# Slave1_flying_pcb_v1.net
KiCad netlist of a schematic drawn in Altium Designer
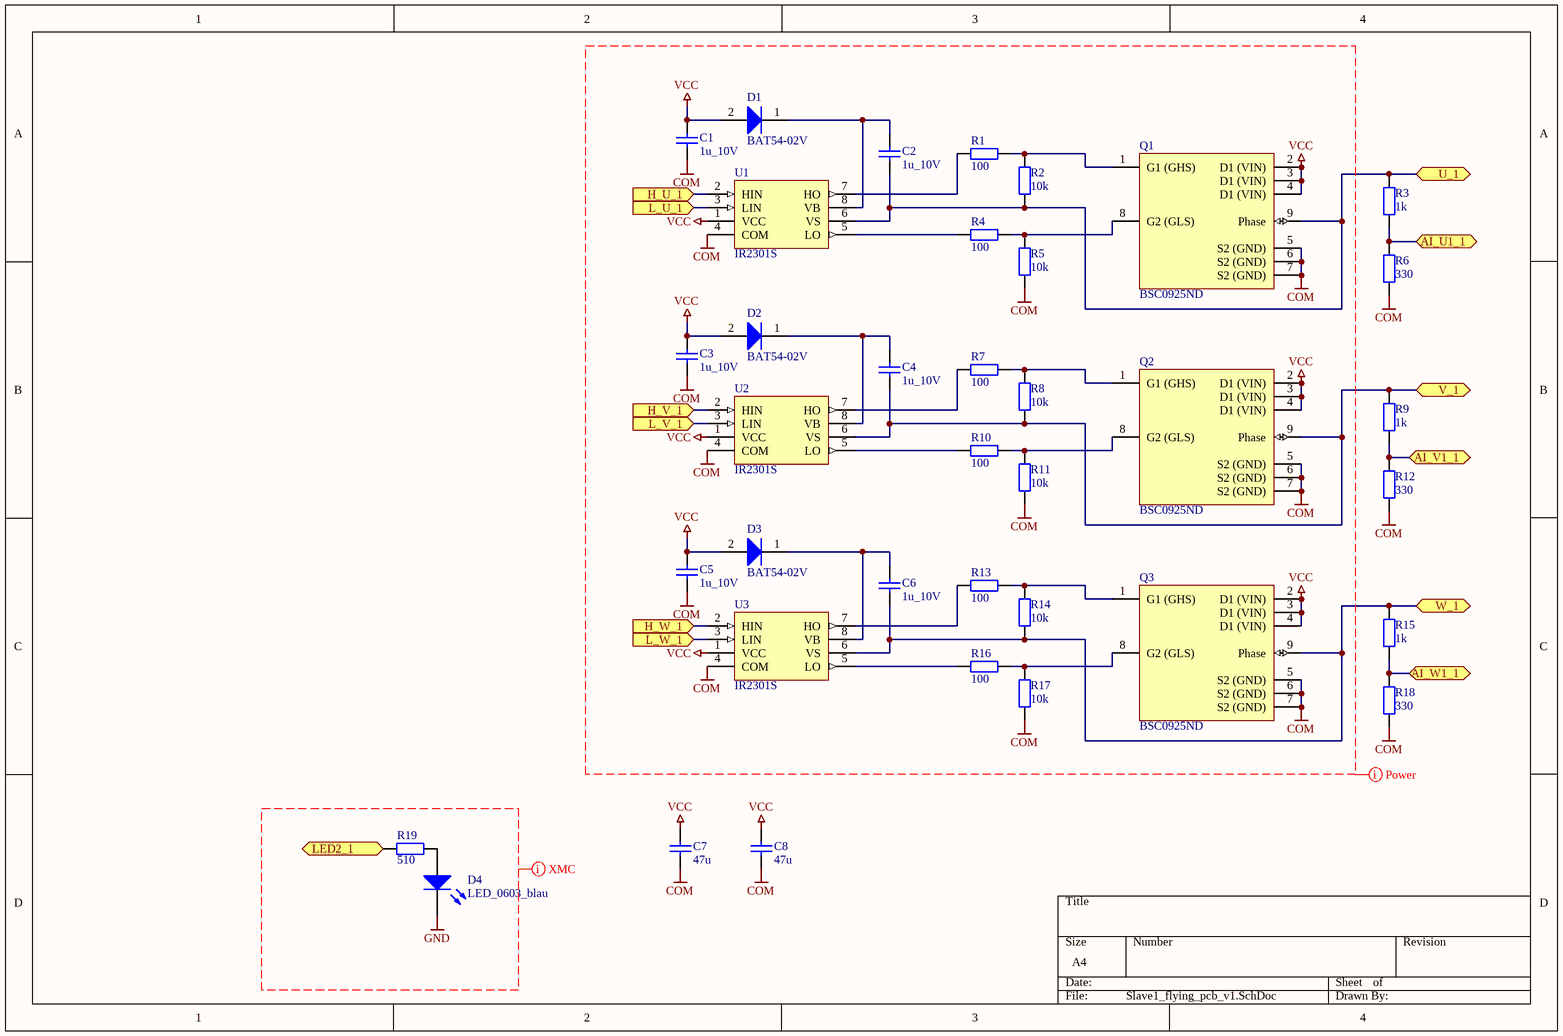
[diagram p0: Slave1_flying_pcb_v1.SchDoc]

(export (version "E")
  (design (tool "Eeschema 10.0.6"))
  (components
    (comp (ref "C1")
      (value "1u_10V")
      (footprint "1608[0603]")
      (fields (field (name "VOLTAGE") "10V"))
      (libsource (lib "Capacitors$") (part "Cap_133"))
    )
    (comp (ref "C2")
      (value "1u_10V")
      (footprint "1608[0603]")
      (fields (field (name "VOLTAGE") "10V"))
      (libsource (lib "Capacitors$") (part "Cap_133"))
    )
    (comp (ref "C3")
      (value "1u_10V")
      (footprint "1608[0603]")
      (fields (field (name "VOLTAGE") "10V"))
      (libsource (lib "Capacitors$") (part "Cap_133"))
    )
    (comp (ref "C4")
      (value "1u_10V")
      (footprint "1608[0603]")
      (fields (field (name "VOLTAGE") "10V"))
      (libsource (lib "Capacitors$") (part "Cap_133"))
    )
    (comp (ref "C5")
      (value "1u_10V")
      (footprint "1608[0603]")
      (fields (field (name "VOLTAGE") "10V"))
      (libsource (lib "Capacitors$") (part "Cap_133"))
    )
    (comp (ref "C6")
      (value "1u_10V")
      (footprint "1608[0603]")
      (fields (field (name "VOLTAGE") "10V"))
      (libsource (lib "Capacitors$") (part "Cap_133"))
    )
    (comp (ref "C7")
      (value "47u")
      (footprint "_0805")
      (fields (field (name "VOLTAGE") "50V"))
      (libsource (lib "Capacitors$") (part "Cap_133"))
    )
    (comp (ref "C8")
      (value "47u")
      (footprint "_0805")
      (fields (field (name "VOLTAGE") "50V"))
      (libsource (lib "Capacitors$") (part "Cap_133"))
    )
    (comp (ref "D1")
      (value "BAT54-02V")
      (footprint "INF-SC79_V")
      (description "Silicon Schottky Diode, SC79, Reel, Green")
      (fields (field (name "MANUFACTURER") "Infineon"))
      (libsource (lib "Pinus_V2") (part "BAT54-02V"))
    )
    (comp (ref "D2")
      (value "BAT54-02V")
      (footprint "INF-SC79_V")
      (description "Silicon Schottky Diode, SC79, Reel, Green")
      (fields (field (name "MANUFACTURER") "Infineon"))
      (libsource (lib "Pinus_V2") (part "BAT54-02V"))
    )
    (comp (ref "D3")
      (value "BAT54-02V")
      (footprint "INF-SC79_V")
      (description "Silicon Schottky Diode, SC79, Reel, Green")
      (fields (field (name "MANUFACTURER") "Infineon"))
      (libsource (lib "Pinus_V2") (part "BAT54-02V"))
    )
    (comp (ref "D4")
      (value "LED_0603_blau")
      (footprint "LED_0603")
      (libsource (lib "flying_pcb_v1") (part "DIODE_60"))
    )
    (comp (ref "Q1")
      (value "BSC0925ND")
      (footprint "INF-PG-TISON-8_V")
      (description "N-Channel OptiMOS Power-MOSFET, 30 V VDS, 40 A ID, -55 to 150 degC, PG-TISON-8, Reel, Green")
      (fields (field (name "MANUFACTURER") "Infineon"))
      (libsource (lib "Pinus_V2") (part "BSC0925ND"))
    )
    (comp (ref "Q2")
      (value "BSC0925ND")
      (footprint "INF-PG-TISON-8_V")
      (description "N-Channel OptiMOS Power-MOSFET, 30 V VDS, 40 A ID, -55 to 150 degC, PG-TISON-8, Reel, Green")
      (fields (field (name "MANUFACTURER") "Infineon"))
      (libsource (lib "Pinus_V2") (part "BSC0925ND"))
    )
    (comp (ref "Q3")
      (value "BSC0925ND")
      (footprint "INF-PG-TISON-8_V")
      (description "N-Channel OptiMOS Power-MOSFET, 30 V VDS, 40 A ID, -55 to 150 degC, PG-TISON-8, Reel, Green")
      (fields (field (name "MANUFACTURER") "Infineon"))
      (libsource (lib "Pinus_V2") (part "BSC0925ND"))
    )
    (comp (ref "R1")
      (value "100")
      (footprint "1608[0603]")
      (fields (field (name "Comment") "Res_0603"))
      (libsource (lib "") (part "Res_6_1"))
    )
    (comp (ref "R2")
      (value "10k")
      (footprint "1608[0603]")
      (fields (field (name "Comment") "Res_0603"))
      (libsource (lib "Resistors$") (part "Res_6"))
    )
    (comp (ref "R3")
      (value "1k")
      (footprint "1608[0603]")
      (fields (field (name "Comment") "Res_0603"))
      (libsource (lib "Resistors$") (part "Res_6"))
    )
    (comp (ref "R4")
      (value "100")
      (footprint "1608[0603]")
      (fields (field (name "Comment") "Res_0603"))
      (libsource (lib "") (part "Res_6_1"))
    )
    (comp (ref "R5")
      (value "10k")
      (footprint "1608[0603]")
      (fields (field (name "Comment") "Res_0603"))
      (libsource (lib "Resistors$") (part "Res_6"))
    )
    (comp (ref "R6")
      (value "330")
      (footprint "1608[0603]")
      (fields (field (name "Comment") "Res_0603"))
      (libsource (lib "Resistors$") (part "Res_6"))
    )
    (comp (ref "R7")
      (value "100")
      (footprint "1608[0603]")
      (fields (field (name "Comment") "Res_0603"))
      (libsource (lib "") (part "Res_6_1"))
    )
    (comp (ref "R8")
      (value "10k")
      (footprint "1608[0603]")
      (fields (field (name "Comment") "Res_0603"))
      (libsource (lib "Resistors$") (part "Res_6"))
    )
    (comp (ref "R9")
      (value "1k")
      (footprint "1608[0603]")
      (fields (field (name "Comment") "Res_0603"))
      (libsource (lib "Resistors$") (part "Res_6"))
    )
    (comp (ref "R10")
      (value "100")
      (footprint "1608[0603]")
      (fields (field (name "Comment") "Res_0603"))
      (libsource (lib "") (part "Res_6_1"))
    )
    (comp (ref "R11")
      (value "10k")
      (footprint "1608[0603]")
      (fields (field (name "Comment") "Res_0603"))
      (libsource (lib "Resistors$") (part "Res_6"))
    )
    (comp (ref "R12")
      (value "330")
      (footprint "1608[0603]")
      (fields (field (name "Comment") "Res_0603"))
      (libsource (lib "Resistors$") (part "Res_6"))
    )
    (comp (ref "R13")
      (value "100")
      (footprint "1608[0603]")
      (fields (field (name "Comment") "Res_0603"))
      (libsource (lib "") (part "Res_6_1"))
    )
    (comp (ref "R14")
      (value "10k")
      (footprint "1608[0603]")
      (fields (field (name "Comment") "Res_0603"))
      (libsource (lib "Resistors$") (part "Res_6"))
    )
    (comp (ref "R15")
      (value "1k")
      (footprint "1608[0603]")
      (fields (field (name "Comment") "Res_0603"))
      (libsource (lib "Resistors$") (part "Res_6"))
    )
    (comp (ref "R16")
      (value "100")
      (footprint "1608[0603]")
      (fields (field (name "Comment") "Res_0603"))
      (libsource (lib "") (part "Res_6_1"))
    )
    (comp (ref "R17")
      (value "10k")
      (footprint "1608[0603]")
      (fields (field (name "Comment") "Res_0603"))
      (libsource (lib "Resistors$") (part "Res_6"))
    )
    (comp (ref "R18")
      (value "330")
      (footprint "1608[0603]")
      (fields (field (name "Comment") "Res_0603"))
      (libsource (lib "Resistors$") (part "Res_6"))
    )
    (comp (ref "R19")
      (value "510")
      (footprint "1608[0603]")
      (fields (field (name "Comment") "Res_0603"))
      (libsource (lib "") (part "Res_6_2"))
    )
    (comp (ref "U1")
      (value "IR2301S")
      (footprint "SO-8_N")
      (description "High and Low Side Driver")
      (fields (field (name "PUBLISHER") "Altium Limited"))
      (libsource (lib "Pinus_V2") (part "IR2101S"))
    )
    (comp (ref "U2")
      (value "IR2301S")
      (footprint "SO-8_N")
      (description "High and Low Side Driver")
      (fields (field (name "PUBLISHER") "Altium Limited"))
      (libsource (lib "Pinus_V2") (part "IR2101S"))
    )
    (comp (ref "U3")
      (value "IR2301S")
      (footprint "SO-8_N")
      (description "High and Low Side Driver")
      (fields (field (name "PUBLISHER") "Altium Limited"))
      (libsource (lib "Pinus_V2") (part "IR2101S"))
    )
  )
  (nets
    (net (code "1") (name "/AI_U1_1") (class "Default")
      (node (ref "R3") (pin "2") (pinfunction "2_2") (pintype "passive"))
      (node (ref "R6") (pin "1") (pinfunction "1_1") (pintype "passive"))
    )
    (net (code "2") (name "/AI_V1_1") (class "Default")
      (node (ref "R12") (pin "1") (pinfunction "1_1") (pintype "passive"))
      (node (ref "R9") (pin "2") (pinfunction "2_2") (pintype "passive"))
    )
    (net (code "3") (name "/AI_W1_1") (class "Default")
      (node (ref "R15") (pin "2") (pinfunction "2_2") (pintype "passive"))
      (node (ref "R18") (pin "1") (pinfunction "1_1") (pintype "passive"))
    )
    (net (code "4") (name "/H_U_1") (class "Default")
      (node (ref "U1") (pin "2") (pinfunction "HIN_2") (pintype "input"))
    )
    (net (code "5") (name "/H_V_1") (class "Default")
      (node (ref "U2") (pin "2") (pinfunction "HIN_2") (pintype "input"))
    )
    (net (code "6") (name "/H_W_1") (class "Default")
      (node (ref "U3") (pin "2") (pinfunction "HIN_2") (pintype "input"))
    )
    (net (code "7") (name "/LED2_1") (class "Default")
      (node (ref "R19") (pin "1") (pinfunction "1_1") (pintype "passive"))
    )
    (net (code "8") (name "/L_U_1") (class "Default")
      (node (ref "U1") (pin "3") (pinfunction "LIN_3") (pintype "input"))
    )
    (net (code "9") (name "/L_V_1") (class "Default")
      (node (ref "U2") (pin "3") (pinfunction "LIN_3") (pintype "input"))
    )
    (net (code "10") (name "/L_W_1") (class "Default")
      (node (ref "U3") (pin "3") (pinfunction "LIN_3") (pintype "input"))
    )
    (net (code "11") (name "/U_1") (class "Default")
      (node (ref "C2") (pin "2") (pinfunction "2_2") (pintype "passive"))
      (node (ref "Q1") (pin "9") (pinfunction "Phase_9") (pintype "bidirectional"))
      (node (ref "R2") (pin "2") (pinfunction "2_2") (pintype "passive"))
      (node (ref "R3") (pin "1") (pinfunction "1_1") (pintype "passive"))
      (node (ref "U1") (pin "6") (pinfunction "VS_6") (pintype "power_in"))
    )
    (net (code "12") (name "/V_1") (class "Default")
      (node (ref "C4") (pin "2") (pinfunction "2_2") (pintype "passive"))
      (node (ref "Q2") (pin "9") (pinfunction "Phase_9") (pintype "bidirectional"))
      (node (ref "R8") (pin "2") (pinfunction "2_2") (pintype "passive"))
      (node (ref "R9") (pin "1") (pinfunction "1_1") (pintype "passive"))
      (node (ref "U2") (pin "6") (pinfunction "VS_6") (pintype "power_in"))
    )
    (net (code "13") (name "/W_1") (class "Default")
      (node (ref "C6") (pin "2") (pinfunction "2_2") (pintype "passive"))
      (node (ref "Q3") (pin "9") (pinfunction "Phase_9") (pintype "bidirectional"))
      (node (ref "R14") (pin "2") (pinfunction "2_2") (pintype "passive"))
      (node (ref "R15") (pin "1") (pinfunction "1_1") (pintype "passive"))
      (node (ref "U3") (pin "6") (pinfunction "VS_6") (pintype "power_in"))
    )
    (net (code "14") (name "COM") (class "Default")
      (node (ref "C1") (pin "2") (pinfunction "2_2") (pintype "passive"))
      (node (ref "C3") (pin "2") (pinfunction "2_2") (pintype "passive"))
      (node (ref "C5") (pin "2") (pinfunction "2_2") (pintype "passive"))
      (node (ref "C7") (pin "1") (pinfunction "1_1") (pintype "passive"))
      (node (ref "C8") (pin "1") (pinfunction "1_1") (pintype "passive"))
      (node (ref "Q1") (pin "5") (pinfunction "S2_(GND)_5") (pintype "passive"))
      (node (ref "Q1") (pin "6") (pinfunction "S2_(GND)_6") (pintype "passive"))
      (node (ref "Q1") (pin "7") (pinfunction "S2_(GND)_7") (pintype "passive"))
      (node (ref "Q2") (pin "5") (pinfunction "S2_(GND)_5") (pintype "passive"))
      (node (ref "Q2") (pin "6") (pinfunction "S2_(GND)_6") (pintype "passive"))
      (node (ref "Q2") (pin "7") (pinfunction "S2_(GND)_7") (pintype "passive"))
      (node (ref "Q3") (pin "5") (pinfunction "S2_(GND)_5") (pintype "passive"))
      (node (ref "Q3") (pin "6") (pinfunction "S2_(GND)_6") (pintype "passive"))
      (node (ref "Q3") (pin "7") (pinfunction "S2_(GND)_7") (pintype "passive"))
      (node (ref "R11") (pin "2") (pinfunction "2_2") (pintype "passive"))
      (node (ref "R12") (pin "2") (pinfunction "2_2") (pintype "passive"))
      (node (ref "R17") (pin "2") (pinfunction "2_2") (pintype "passive"))
      (node (ref "R18") (pin "2") (pinfunction "2_2") (pintype "passive"))
      (node (ref "R5") (pin "2") (pinfunction "2_2") (pintype "passive"))
      (node (ref "R6") (pin "2") (pinfunction "2_2") (pintype "passive"))
      (node (ref "U1") (pin "4") (pinfunction "COM_4") (pintype "power_in"))
      (node (ref "U2") (pin "4") (pinfunction "COM_4") (pintype "power_in"))
      (node (ref "U3") (pin "4") (pinfunction "COM_4") (pintype "power_in"))
    )
    (net (code "15") (name "GND") (class "Default")
      (node (ref "D4") (pin "2") (pinfunction "2_2") (pintype "passive"))
    )
    (net (code "16") (name "Net-(D1-K)") (class "Default")
      (node (ref "C2") (pin "1") (pinfunction "1_1") (pintype "passive"))
      (node (ref "D1") (pin "1") (pinfunction "K_1") (pintype "passive"))
      (node (ref "U1") (pin "8") (pinfunction "VB_8") (pintype "power_in"))
    )
    (net (code "17") (name "Net-(D2-K)") (class "Default")
      (node (ref "C4") (pin "1") (pinfunction "1_1") (pintype "passive"))
      (node (ref "D2") (pin "1") (pinfunction "K_1") (pintype "passive"))
      (node (ref "U2") (pin "8") (pinfunction "VB_8") (pintype "power_in"))
    )
    (net (code "18") (name "Net-(D3-K)") (class "Default")
      (node (ref "C6") (pin "1") (pinfunction "1_1") (pintype "passive"))
      (node (ref "D3") (pin "1") (pinfunction "K_1") (pintype "passive"))
      (node (ref "U3") (pin "8") (pinfunction "VB_8") (pintype "power_in"))
    )
    (net (code "19") (name "Net-(D4-Pad1)") (class "Default")
      (node (ref "D4") (pin "1") (pinfunction "1_1") (pintype "passive"))
      (node (ref "R19") (pin "2") (pinfunction "2_2") (pintype "passive"))
    )
    (net (code "20") (name "Net-(Q1-G1_(GHS))") (class "Default")
      (node (ref "Q1") (pin "1") (pinfunction "G1_(GHS)_1") (pintype "passive"))
      (node (ref "R1") (pin "1") (pinfunction "1_1") (pintype "passive"))
      (node (ref "R2") (pin "1") (pinfunction "1_1") (pintype "passive"))
    )
    (net (code "21") (name "Net-(Q1-G2_(GLS))") (class "Default")
      (node (ref "Q1") (pin "8") (pinfunction "G2_(GLS)_8") (pintype "passive"))
      (node (ref "R4") (pin "1") (pinfunction "1_1") (pintype "passive"))
      (node (ref "R5") (pin "1") (pinfunction "1_1") (pintype "passive"))
    )
    (net (code "22") (name "Net-(Q2-G1_(GHS))") (class "Default")
      (node (ref "Q2") (pin "1") (pinfunction "G1_(GHS)_1") (pintype "passive"))
      (node (ref "R7") (pin "1") (pinfunction "1_1") (pintype "passive"))
      (node (ref "R8") (pin "1") (pinfunction "1_1") (pintype "passive"))
    )
    (net (code "23") (name "Net-(Q2-G2_(GLS))") (class "Default")
      (node (ref "Q2") (pin "8") (pinfunction "G2_(GLS)_8") (pintype "passive"))
      (node (ref "R10") (pin "1") (pinfunction "1_1") (pintype "passive"))
      (node (ref "R11") (pin "1") (pinfunction "1_1") (pintype "passive"))
    )
    (net (code "24") (name "Net-(Q3-G1_(GHS))") (class "Default")
      (node (ref "Q3") (pin "1") (pinfunction "G1_(GHS)_1") (pintype "passive"))
      (node (ref "R13") (pin "1") (pinfunction "1_1") (pintype "passive"))
      (node (ref "R14") (pin "1") (pinfunction "1_1") (pintype "passive"))
    )
    (net (code "25") (name "Net-(Q3-G2_(GLS))") (class "Default")
      (node (ref "Q3") (pin "8") (pinfunction "G2_(GLS)_8") (pintype "passive"))
      (node (ref "R16") (pin "1") (pinfunction "1_1") (pintype "passive"))
      (node (ref "R17") (pin "1") (pinfunction "1_1") (pintype "passive"))
    )
    (net (code "26") (name "Net-(U1-HO)") (class "Default")
      (node (ref "R1") (pin "2") (pinfunction "2_2") (pintype "passive"))
      (node (ref "U1") (pin "7") (pinfunction "HO_7") (pintype "output"))
    )
    (net (code "27") (name "Net-(U1-LO)") (class "Default")
      (node (ref "R4") (pin "2") (pinfunction "2_2") (pintype "passive"))
      (node (ref "U1") (pin "5") (pinfunction "LO_5") (pintype "output"))
    )
    (net (code "28") (name "Net-(U2-HO)") (class "Default")
      (node (ref "R7") (pin "2") (pinfunction "2_2") (pintype "passive"))
      (node (ref "U2") (pin "7") (pinfunction "HO_7") (pintype "output"))
    )
    (net (code "29") (name "Net-(U2-LO)") (class "Default")
      (node (ref "R10") (pin "2") (pinfunction "2_2") (pintype "passive"))
      (node (ref "U2") (pin "5") (pinfunction "LO_5") (pintype "output"))
    )
    (net (code "30") (name "Net-(U3-HO)") (class "Default")
      (node (ref "R13") (pin "2") (pinfunction "2_2") (pintype "passive"))
      (node (ref "U3") (pin "7") (pinfunction "HO_7") (pintype "output"))
    )
    (net (code "31") (name "Net-(U3-LO)") (class "Default")
      (node (ref "R16") (pin "2") (pinfunction "2_2") (pintype "passive"))
      (node (ref "U3") (pin "5") (pinfunction "LO_5") (pintype "output"))
    )
    (net (code "32") (name "VCC") (class "Default")
      (node (ref "C1") (pin "1") (pinfunction "1_1") (pintype "passive"))
      (node (ref "C3") (pin "1") (pinfunction "1_1") (pintype "passive"))
      (node (ref "C5") (pin "1") (pinfunction "1_1") (pintype "passive"))
      (node (ref "C7") (pin "2") (pinfunction "2_2") (pintype "passive"))
      (node (ref "C8") (pin "2") (pinfunction "2_2") (pintype "passive"))
      (node (ref "D1") (pin "2") (pinfunction "A_2") (pintype "passive"))
      (node (ref "D2") (pin "2") (pinfunction "A_2") (pintype "passive"))
      (node (ref "D3") (pin "2") (pinfunction "A_2") (pintype "passive"))
      (node (ref "Q1") (pin "2") (pinfunction "D1_(VIN)_2") (pintype "passive"))
      (node (ref "Q1") (pin "3") (pinfunction "D1_(VIN)_3") (pintype "passive"))
      (node (ref "Q1") (pin "4") (pinfunction "D1_(VIN)_4") (pintype "passive"))
      (node (ref "Q2") (pin "2") (pinfunction "D1_(VIN)_2") (pintype "passive"))
      (node (ref "Q2") (pin "3") (pinfunction "D1_(VIN)_3") (pintype "passive"))
      (node (ref "Q2") (pin "4") (pinfunction "D1_(VIN)_4") (pintype "passive"))
      (node (ref "Q3") (pin "2") (pinfunction "D1_(VIN)_2") (pintype "passive"))
      (node (ref "Q3") (pin "3") (pinfunction "D1_(VIN)_3") (pintype "passive"))
      (node (ref "Q3") (pin "4") (pinfunction "D1_(VIN)_4") (pintype "passive"))
      (node (ref "U1") (pin "1") (pinfunction "VCC_1") (pintype "power_in"))
      (node (ref "U2") (pin "1") (pinfunction "VCC_1") (pintype "power_in"))
      (node (ref "U3") (pin "1") (pinfunction "VCC_1") (pintype "power_in"))
    )
  )
)
